# TPS54331_3A.net
KiCad netlist of a schematic drawn in Altium Designer
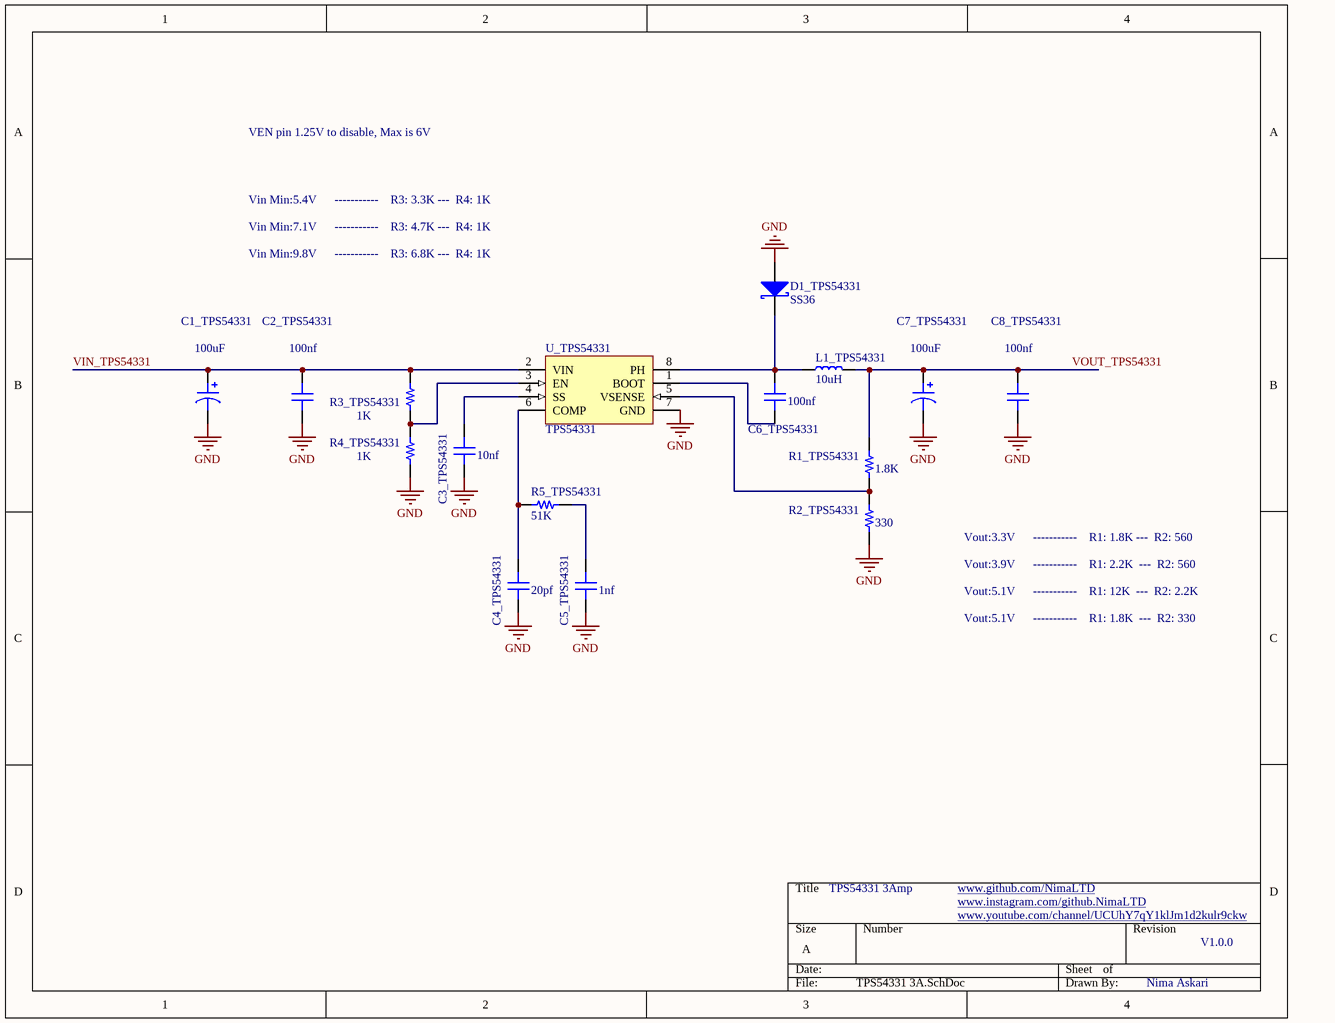
[diagram p0: TPS54331 3A.SchDoc]

(export (version "E")
  (design (tool "Eeschema 10.0.6"))
  (components
    (comp (ref "C1_TPS54331")
      (value "100uF")
      (footprint "CAP AL SMD D6 H6")
      (description "SMT Polarised Capacitor")
      (libsource (lib "CAPACITOR") (part "Pol Cap SMD AL D6 H6"))
    )
    (comp (ref "C2_TPS54331")
      (value "100nf")
      (footprint "CAP 1206")
      (description "SMT Capacitor")
      (libsource (lib "CAPACITOR") (part "Cap SMD 1206"))
    )
    (comp (ref "C3_TPS54331")
      (value "10nf")
      (footprint "CAP 0805")
      (description "SMT Capacitor")
      (libsource (lib "CAPACITOR") (part "Cap SMD 0805"))
    )
    (comp (ref "C4_TPS54331")
      (value "20pf")
      (footprint "CAP 0805")
      (description "SMT Capacitor")
      (libsource (lib "CAPACITOR") (part "Cap SMD 0805"))
    )
    (comp (ref "C5_TPS54331")
      (value "1nf")
      (footprint "CAP 0805")
      (description "SMT Capacitor")
      (libsource (lib "CAPACITOR") (part "Cap SMD 0805"))
    )
    (comp (ref "C6_TPS54331")
      (value "100nf")
      (footprint "CAP 0805")
      (description "SMT Capacitor")
      (libsource (lib "CAPACITOR") (part "Cap SMD 0805"))
    )
    (comp (ref "C7_TPS54331")
      (value "100uF")
      (footprint "CAP AL SMD D6 H6")
      (description "SMT Polarised Capacitor")
      (libsource (lib "CAPACITOR") (part "Pol Cap SMD AL D6 H6"))
    )
    (comp (ref "C8_TPS54331")
      (value "100nf")
      (footprint "CAP 0805")
      (description "SMT Capacitor")
      (libsource (lib "CAPACITOR") (part "Cap SMD 0805"))
    )
    (comp (ref "D1_TPS54331")
      (value "SS36 SMD")
      (footprint "DO214AB SMC")
      (description "3A Schottky")
      (fields (field (name "PARAMETER 1") "SS36"))
      (libsource (lib "DIODE") (part "SS36 SMD"))
    )
    (comp (ref "L1_TPS54331")
      (value "10uH")
      (footprint "IND 12X12")
      (description "SMT Inductor")
      (fields (field (name "Comment") "Inductor SMD POWER 12X12mm"))
      (libsource (lib "INDUCTOR") (part "Inductor SMD POWER 12X12mm"))
    )
    (comp (ref "R1_TPS54331")
      (value "1.8K")
      (footprint "RES 0805")
      (description "SMD Resistor")
      (libsource (lib "RESISTOR") (part "Res SMD 0805"))
    )
    (comp (ref "R2_TPS54331")
      (value "330")
      (footprint "RES 0805")
      (description "SMD Resistor")
      (libsource (lib "RESISTOR") (part "Res SMD 0805"))
    )
    (comp (ref "R3_TPS54331")
      (value "1K")
      (footprint "RES 0805")
      (description "SMD Resistor")
      (libsource (lib "RESISTOR") (part "Res SMD 0805"))
    )
    (comp (ref "R4_TPS54331")
      (value "1K")
      (footprint "RES 0805")
      (description "SMD Resistor")
      (libsource (lib "RESISTOR") (part "Res SMD 0805"))
    )
    (comp (ref "R5_TPS54331")
      (value "51K")
      (footprint "RES 0805")
      (description "SMD Resistor")
      (libsource (lib "RESISTOR") (part "Res SMD 0805"))
    )
    (comp (ref "U_TPS54331")
      (value "TPS54331")
      (footprint "SOP8")
      (fields (field (name "PARTNUMBER") "TPS54331"))
      (libsource (lib "IC") (part "TPS54331"))
    )
  )
  (nets
    (net (code "1") (name "/VIN_TPS54331") (class "Default")
      (node (ref "C1_TPS54331") (pin "1") (pinfunction "1_1") (pintype "passive"))
      (node (ref "C2_TPS54331") (pin "2") (pinfunction "2_2") (pintype "passive"))
      (node (ref "R3_TPS54331") (pin "2") (pinfunction "2_2") (pintype "passive"))
      (node (ref "U_TPS54331") (pin "2") (pinfunction "VIN_2") (pintype "power_in"))
    )
    (net (code "2") (name "/VOUT_TPS54331") (class "Default")
      (node (ref "C7_TPS54331") (pin "1") (pinfunction "1_1") (pintype "passive"))
      (node (ref "C8_TPS54331") (pin "2") (pinfunction "2_2") (pintype "passive"))
      (node (ref "L1_TPS54331") (pin "2") (pinfunction "2_2") (pintype "passive"))
      (node (ref "R1_TPS54331") (pin "2") (pinfunction "2_2") (pintype "passive"))
    )
    (net (code "3") (name "GND") (class "Default")
      (node (ref "C1_TPS54331") (pin "2") (pinfunction "2_2") (pintype "passive"))
      (node (ref "C2_TPS54331") (pin "1") (pinfunction "1_1") (pintype "passive"))
      (node (ref "C3_TPS54331") (pin "1") (pinfunction "1_1") (pintype "passive"))
      (node (ref "C4_TPS54331") (pin "1") (pinfunction "1_1") (pintype "passive"))
      (node (ref "C5_TPS54331") (pin "1") (pinfunction "1_1") (pintype "passive"))
      (node (ref "C7_TPS54331") (pin "2") (pinfunction "2_2") (pintype "passive"))
      (node (ref "C8_TPS54331") (pin "1") (pinfunction "1_1") (pintype "passive"))
      (node (ref "D1_TPS54331") (pin "1") (pinfunction "A_1") (pintype "passive"))
      (node (ref "R2_TPS54331") (pin "1") (pinfunction "1_1") (pintype "passive"))
      (node (ref "R4_TPS54331") (pin "1") (pinfunction "1_1") (pintype "passive"))
      (node (ref "U_TPS54331") (pin "7") (pinfunction "GND_7") (pintype "power_in"))
    )
    (net (code "4") (name "Net-(C5_TPS54331-Pad2)") (class "Default")
      (node (ref "C5_TPS54331") (pin "2") (pinfunction "2_2") (pintype "passive"))
      (node (ref "R5_TPS54331") (pin "1") (pinfunction "1_1") (pintype "passive"))
    )
    (net (code "5") (name "Net-(D1_TPS54331-K)") (class "Default")
      (node (ref "C6_TPS54331") (pin "2") (pinfunction "2_2") (pintype "passive"))
      (node (ref "D1_TPS54331") (pin "2") (pinfunction "K_2") (pintype "passive"))
      (node (ref "L1_TPS54331") (pin "1") (pinfunction "1_1") (pintype "passive"))
      (node (ref "U_TPS54331") (pin "8") (pinfunction "PH_8") (pintype "power_in"))
    )
    (net (code "6") (name "Net-(U_TPS54331-BOOT)") (class "Default")
      (node (ref "C6_TPS54331") (pin "1") (pinfunction "1_1") (pintype "passive"))
      (node (ref "U_TPS54331") (pin "1") (pinfunction "BOOT_1") (pintype "passive"))
    )
    (net (code "7") (name "Net-(U_TPS54331-COMP)") (class "Default")
      (node (ref "C4_TPS54331") (pin "2") (pinfunction "2_2") (pintype "passive"))
      (node (ref "R5_TPS54331") (pin "2") (pinfunction "2_2") (pintype "passive"))
      (node (ref "U_TPS54331") (pin "6") (pinfunction "COMP_6") (pintype "passive"))
    )
    (net (code "8") (name "Net-(U_TPS54331-EN)") (class "Default")
      (node (ref "R3_TPS54331") (pin "1") (pinfunction "1_1") (pintype "passive"))
      (node (ref "R4_TPS54331") (pin "2") (pinfunction "2_2") (pintype "passive"))
      (node (ref "U_TPS54331") (pin "3") (pinfunction "EN_3") (pintype "input"))
    )
    (net (code "9") (name "Net-(U_TPS54331-SS)") (class "Default")
      (node (ref "C3_TPS54331") (pin "2") (pinfunction "2_2") (pintype "passive"))
      (node (ref "U_TPS54331") (pin "4") (pinfunction "SS_4") (pintype "input"))
    )
    (net (code "10") (name "Net-(U_TPS54331-VSENSE)") (class "Default")
      (node (ref "R1_TPS54331") (pin "1") (pinfunction "1_1") (pintype "passive"))
      (node (ref "R2_TPS54331") (pin "2") (pinfunction "2_2") (pintype "passive"))
      (node (ref "U_TPS54331") (pin "5") (pinfunction "VSENSE_5") (pintype "input"))
    )
  )
)
